# BluetoothAdapter4_0.net
KiCad netlist of a schematic drawn in Altium Designer
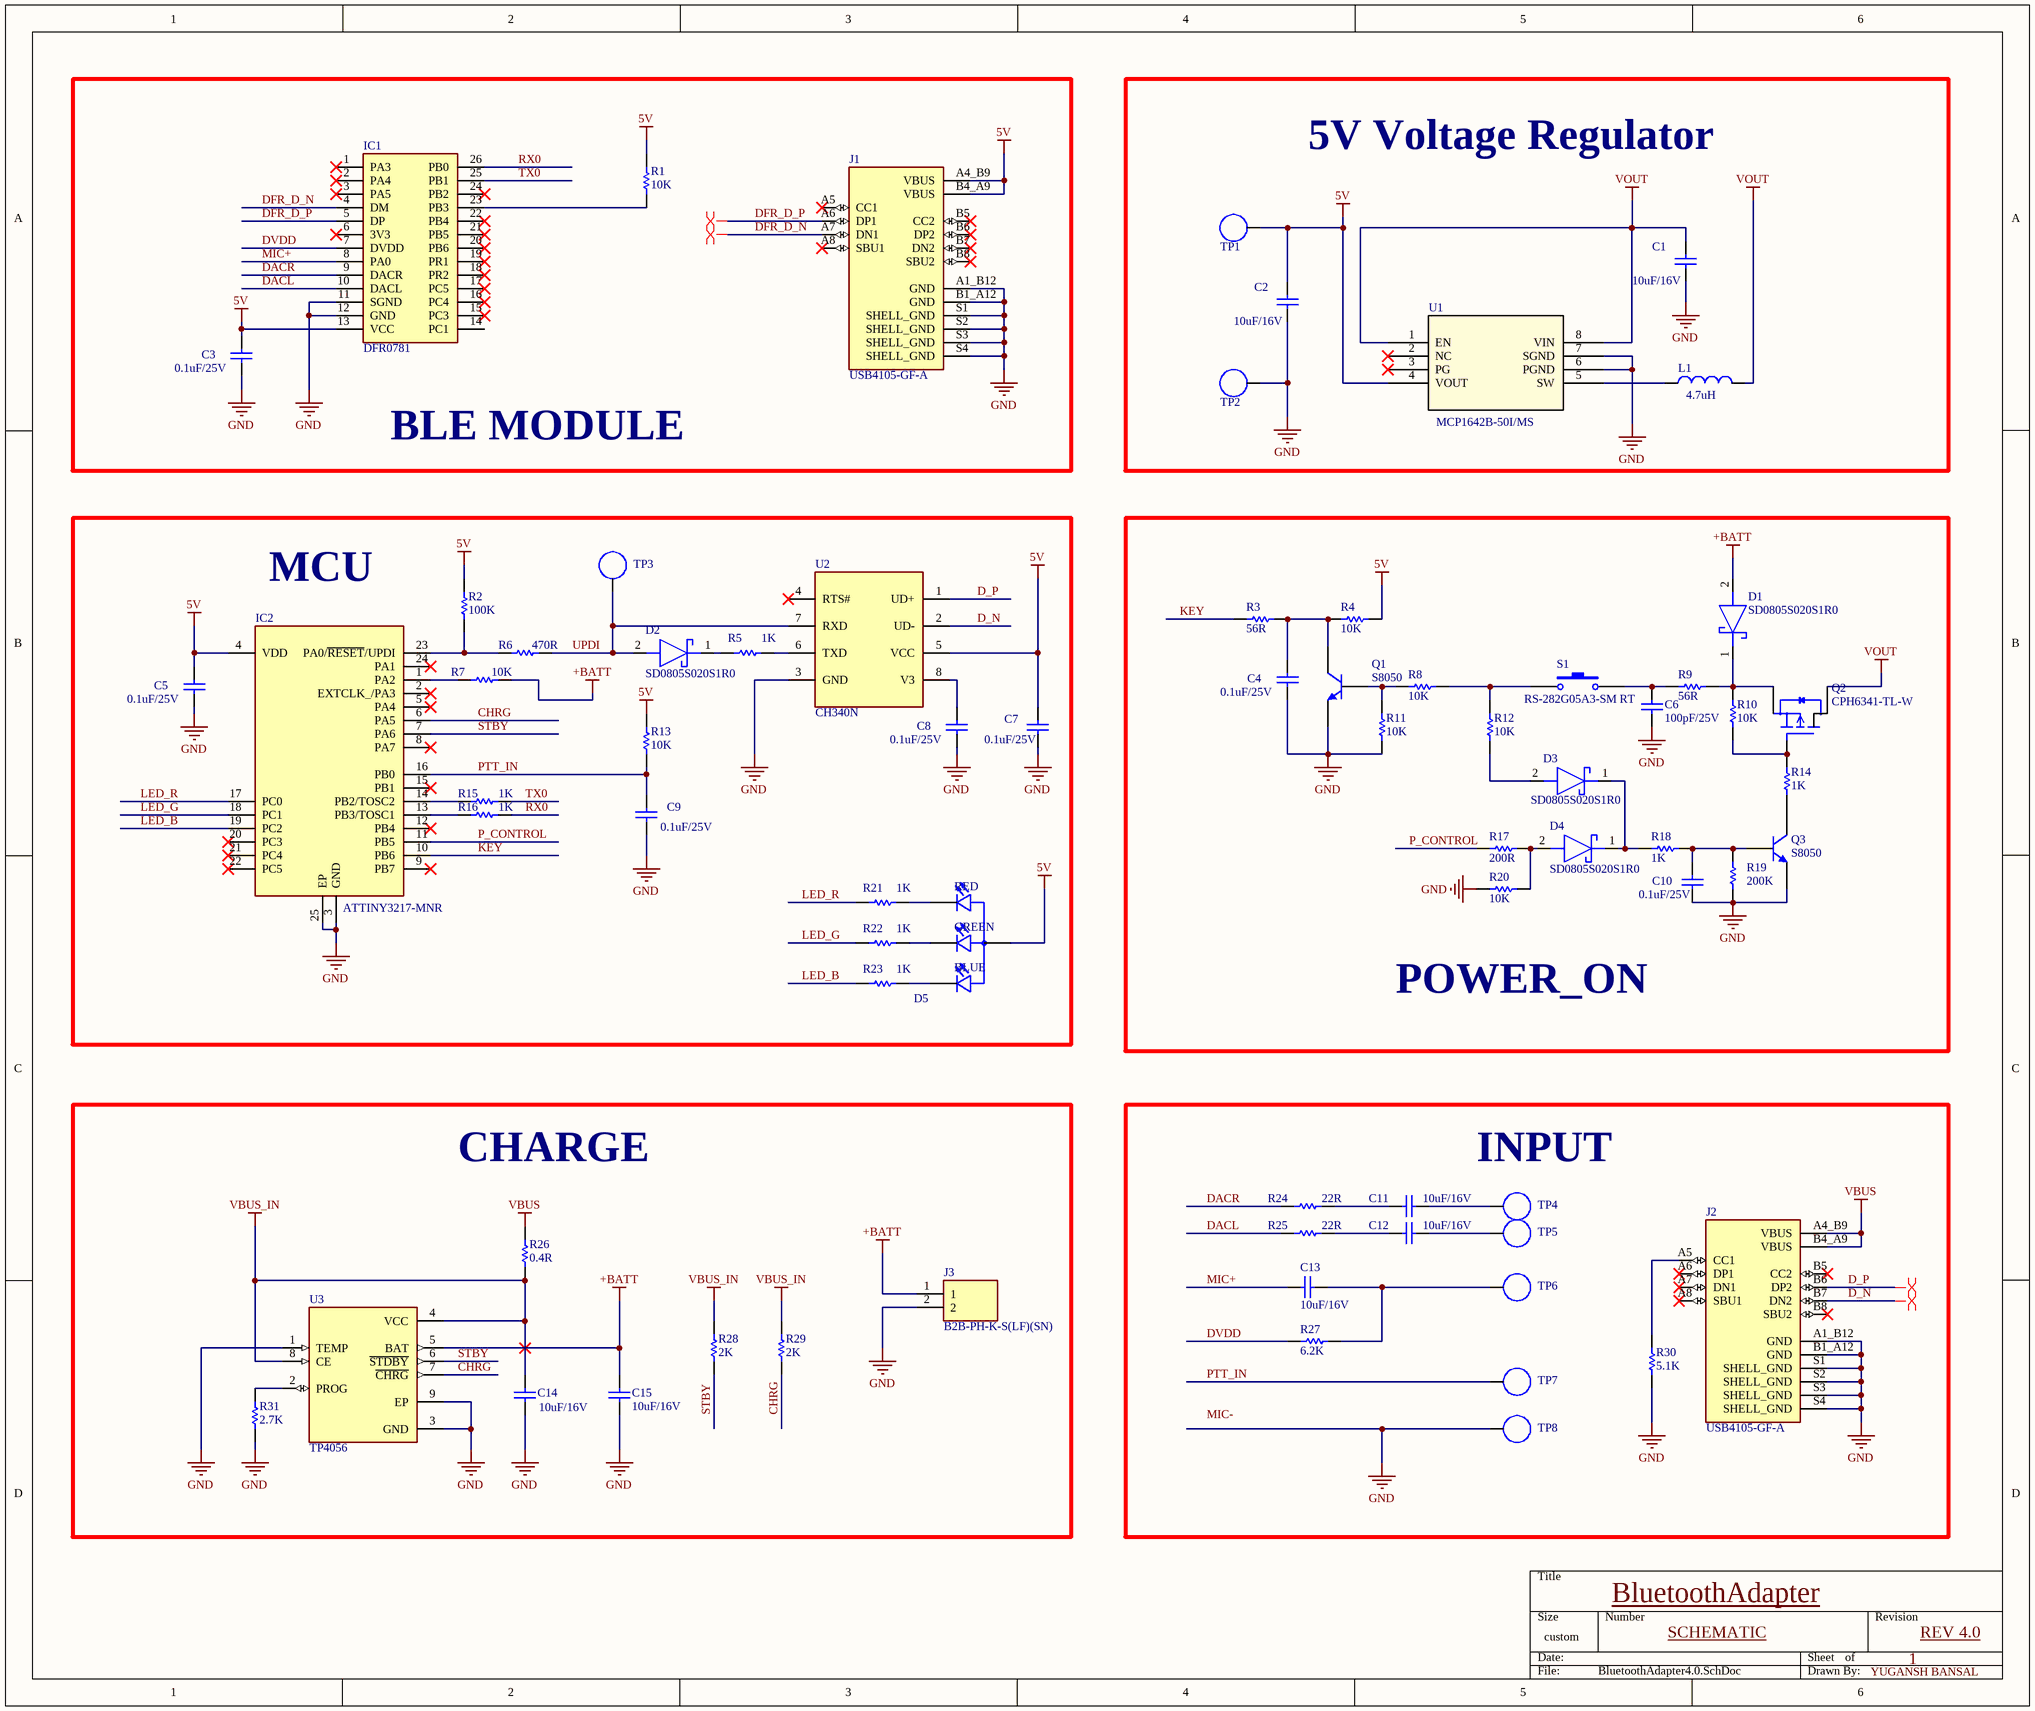
[diagram p0: BluetoothAdapter4.0.SchDoc]

(export (version "E")
  (design (tool "Eeschema 10.0.6"))
  (components
    (comp (ref "C1")
      (value "10uF/16V")
      (footprint "BluetoothAdapter:C0603S")
      (description "10 µF ±20% 16V Ceramic Capacitor X5R 0603 (1608 Metric)")
      (fields
        (field (name "MANUFACTURER") "Murata Electronics")
        (field (name "DIGI-KEY PART NUMBER") "490-10729-6-ND")
      )
      (libsource (lib "myLib") (part "Cap"))
    )
    (comp (ref "C2")
      (value "10uF/16V")
      (footprint "BluetoothAdapter:C0603S")
      (description "10 µF ±20% 16V Ceramic Capacitor X5R 0603 (1608 Metric)")
      (fields
        (field (name "MANUFACTURER") "Murata Electronics")
        (field (name "DIGI-KEY PART NUMBER") "490-10729-6-ND")
      )
      (libsource (lib "myLib") (part "Cap"))
    )
    (comp (ref "C3")
      (value "0.1uF/25V")
      (footprint "BluetoothAdapter:C0603S")
      (description "0.1 µF ±10% 25V Ceramic Capacitor X7R 0603 (1608 Metric)")
      (fields
        (field (name "MANUFACTURER") "KEMET")
        (field (name "DIGI-KEY PART NUMBER") "399-C0603C104K3RAC7867TR-ND")
      )
      (libsource (lib "myLib") (part "Cap"))
    )
    (comp (ref "C4")
      (value "0.1uF/25V")
      (footprint "BluetoothAdapter:C0603S")
      (description "0.1 µF ±10% 25V Ceramic Capacitor X7R 0603 (1608 Metric)")
      (fields
        (field (name "MANUFACTURER") "KEMET")
        (field (name "DIGI-KEY PART NUMBER") "399-C0603C104K3RAC7867TR-ND")
      )
      (libsource (lib "myLib") (part "Cap"))
    )
    (comp (ref "C5")
      (value "0.1uF/25V")
      (footprint "BluetoothAdapter:C0603S")
      (description "0.1 µF ±10% 25V Ceramic Capacitor X7R 0603 (1608 Metric)")
      (fields
        (field (name "MANUFACTURER") "KEMET")
        (field (name "DIGI-KEY PART NUMBER") "399-C0603C104K3RAC7867TR-ND")
      )
      (libsource (lib "myLib") (part "Cap"))
    )
    (comp (ref "C6")
      (value "100pF/25V")
      (footprint "BluetoothAdapter:C0603S")
      (description "0.1 µF ±10% 25V Ceramic Capacitor X7R 0603 (1608 Metric)")
      (fields
        (field (name "MANUFACTURER") "KEMET")
        (field (name "DIGI-KEY PART NUMBER") "399-C0603C101K3RACAUTODKR-ND")
      )
      (libsource (lib "myLib") (part "Cap"))
    )
    (comp (ref "C7")
      (value "0.1uF/25V")
      (footprint "BluetoothAdapter:C0603S")
      (description "0.1 µF ±10% 25V Ceramic Capacitor X7R 0603 (1608 Metric)")
      (fields
        (field (name "MANUFACTURER") "KEMET")
        (field (name "DIGI-KEY PART NUMBER") "399-C0603C104K3RAC7867TR-ND")
      )
      (libsource (lib "myLib") (part "Cap"))
    )
    (comp (ref "C8")
      (value "0.1uF/25V")
      (footprint "BluetoothAdapter:C0603S")
      (description "0.1 µF ±10% 25V Ceramic Capacitor X7R 0603 (1608 Metric)")
      (fields
        (field (name "MANUFACTURER") "KEMET")
        (field (name "DIGI-KEY PART NUMBER") "399-C0603C104K3RAC7867TR-ND")
      )
      (libsource (lib "myLib") (part "Cap"))
    )
    (comp (ref "C9")
      (value "0.1uF/25V")
      (footprint "BluetoothAdapter:C0603S")
      (description "0.1 µF ±10% 25V Ceramic Capacitor X7R 0603 (1608 Metric)")
      (fields
        (field (name "MANUFACTURER") "KEMET")
        (field (name "DIGI-KEY PART NUMBER") "399-C0603C104K3RAC7867TR-ND")
      )
      (libsource (lib "myLib") (part "Cap"))
    )
    (comp (ref "C10")
      (value "0.1uF/25V")
      (footprint "BluetoothAdapter:C0603S")
      (description "0.1 µF ±10% 25V Ceramic Capacitor X7R 0603 (1608 Metric)")
      (fields
        (field (name "MANUFACTURER") "KEMET")
        (field (name "DIGI-KEY PART NUMBER") "399-C0603C104K3RAC7867TR-ND")
      )
      (libsource (lib "myLib") (part "Cap"))
    )
    (comp (ref "C11")
      (value "10uF/16V")
      (footprint "BluetoothAdapter:C0603S")
      (description "10 µF ±20% 16V Ceramic Capacitor X5R 0603 (1608 Metric)")
      (fields
        (field (name "MANUFACTURER") "Murata Electronics")
        (field (name "DIGI-KEY PART NUMBER") "490-10729-6-ND")
      )
      (libsource (lib "myLib") (part "Cap"))
    )
    (comp (ref "C12")
      (value "10uF/16V")
      (footprint "BluetoothAdapter:C0603S")
      (description "10 µF ±20% 16V Ceramic Capacitor X5R 0603 (1608 Metric)")
      (fields
        (field (name "MANUFACTURER") "Murata Electronics")
        (field (name "DIGI-KEY PART NUMBER") "490-10729-6-ND")
      )
      (libsource (lib "myLib") (part "Cap"))
    )
    (comp (ref "C13")
      (value "10uF/16V")
      (footprint "BluetoothAdapter:C0603S")
      (description "10 µF ±20% 16V Ceramic Capacitor X5R 0603 (1608 Metric)")
      (fields
        (field (name "MANUFACTURER") "Murata Electronics")
        (field (name "DIGI-KEY PART NUMBER") "490-10729-6-ND")
      )
      (libsource (lib "myLib") (part "Cap"))
    )
    (comp (ref "C14")
      (value "10uF/16V")
      (footprint "BluetoothAdapter:C0603S")
      (description "10 µF ±20% 16V Ceramic Capacitor X5R 0603 (1608 Metric)")
      (fields
        (field (name "MANUFACTURER") "Murata Electronics")
        (field (name "DIGI-KEY PART NUMBER") "490-10729-6-ND")
      )
      (libsource (lib "myLib") (part "Cap"))
    )
    (comp (ref "C15")
      (value "10uF/16V")
      (footprint "BluetoothAdapter:C0603S")
      (description "10 µF ±20% 16V Ceramic Capacitor X5R 0603 (1608 Metric)")
      (fields
        (field (name "MANUFACTURER") "Murata Electronics")
        (field (name "DIGI-KEY PART NUMBER") "490-10729-6-ND")
      )
      (libsource (lib "myLib") (part "Cap"))
    )
    (comp (ref "D1")
      (value "SD0805S020S1R0")
      (footprint "BluetoothAdapter:DIOM1613X100N")
      (description "Diode 20 V 1A Surface Mount 0805 (2012 Metric)")
      (fields (field (name "MANUFACTURER") "AVX") (field (name "DIGI-KEY PART NUMBER") "581-SD0805S020S1R0"))
      (libsource (lib "*") (part "SD0805S020S1R0"))
    )
    (comp (ref "D2")
      (value "SD0805S020S1R0")
      (footprint "BluetoothAdapter:DIOM1613X100N")
      (description "Diode 20 V 1A Surface Mount 0805 (2012 Metric)")
      (fields (field (name "MANUFACTURER") "AVX") (field (name "DIGI-KEY PART NUMBER") "581-SD0805S020S1R0"))
      (libsource (lib "*") (part "SD0805S020S1R0"))
    )
    (comp (ref "D3")
      (value "SD0805S020S1R0")
      (footprint "BluetoothAdapter:DIOM1613X100N")
      (description "Diode 20 V 1A Surface Mount 0805 (2012 Metric)")
      (fields (field (name "MANUFACTURER") "AVX") (field (name "DIGI-KEY PART NUMBER") "581-SD0805S020S1R0"))
      (libsource (lib "*") (part "SD0805S020S1R0"))
    )
    (comp (ref "D4")
      (value "SD0805S020S1R0")
      (footprint "BluetoothAdapter:DIOM1613X100N")
      (description "Diode 20 V 1A Surface Mount 0805 (2012 Metric)")
      (fields (field (name "MANUFACTURER") "AVX") (field (name "DIGI-KEY PART NUMBER") "581-SD0805S020S1R0"))
      (libsource (lib "*") (part "SD0805S020S1R0"))
    )
    (comp (ref "D5")
      (value "LED RGB MIXED WHITE ( 1.6(L)X1.6")
      (footprint "BluetoothAdapter:LED_B38G3RGB-10D0003H2U1930")
      (description "Red, Green, Blue (RGB) LED Indication - Discrete 2V Red, 3V Green, 3V Blue 0606 (1616 Metric)")
      (fields
        (field (name "MANUFACTURER") "Harvatek Corporation")
        (field (name "DIGI-KEY PART NUMBER") "3147-B38G3RGB-10D0003H2U1930DKR-ND")
      )
      (libsource (lib "BluetoothAdapter") (part "B38G3RGB-10D0003H2U1930"))
    )
    (comp (ref "IC1")
      (value "DFR0781")
      (footprint "BluetoothAdapter:DFR0781")
      (description "Bluetooth Bluetooth v5.0 Transceiver Module Antenna Not Included Surface Mount")
      (fields (field (name "MANUFACTURER") "DFRobot") (field (name "DIGI-KEY PART NUMBER") "1738-DFR0781-ND"))
      (libsource (lib "BluetoothAdapter") (part "DFR0781"))
    )
    (comp (ref "IC2")
      (value "ATTINY3217-MNR")
      (footprint "BluetoothAdapter:QFN50P400X400X90-25N-D")
      (fields
        (field (name "MANUFACTURER") "Microchip")
        (field (name "DIGI-KEY PART NUMBER") "ATTINY3217-MNRDKR-ND")
        (field (name "Comment") "IC MCU 8BIT 32KB FLASH 24VQFN")
      )
      (libsource (lib "BluetoothAdapter") (part "ATTINY3217-MNR"))
    )
    (comp (ref "J1")
      (value "USB4105-GF-A")
      (footprint "BluetoothAdapter:GCT_USB4105-GF-A")
      (fields
        (field (name "MANUFACTURER") "GCT")
        (field (name "DIGI-KEY PART NUMBER") "2073-USB4105-GF-ADKR-ND")
        (field (name "Comment") "CONN RCP USB2.0 TYP C 24P SMD RA")
      )
      (libsource (lib "BluetoothAdapter") (part "USB4105-GF-A"))
    )
    (comp (ref "J2")
      (value "USB4105-GF-A")
      (footprint "BluetoothAdapter:GCT_USB4105-GF-A")
      (fields
        (field (name "MANUFACTURER") "GCT")
        (field (name "DIGI-KEY PART NUMBER") "2073-USB4105-GF-ADKR-ND")
        (field (name "Comment") "CONN RCP USB2.0 TYP C 24P SMD RA")
      )
      (libsource (lib "BluetoothAdapter") (part "USB4105-GF-A"))
    )
    (comp (ref "J3")
      (value "B2B-PH-K-S(LF)(SN)")
      (footprint "BluetoothAdapter:SHDR2W50P0X200_1X2_590X450X600P")
      (description "Connector Header Through Hole 2 position 0.079\" (2.00mm)")
      (fields
        (field (name "MANUFACTURER") "JST Sales America Inc.")
        (field (name "DIGI-KEY PART NUMBER") "455-1704-ND")
      )
      (libsource (lib "BluetoothAdapter") (part "B2B-PH-K-S(LF)(SN)"))
    )
    (comp (ref "L1")
      (value "4.7uH")
      (footprint "BluetoothAdapter:INDC2520X100N")
      (description "4.7 µH Shielded Multilayer Inductor 1.3 A 120mOhm 1008 (2520 Metric)")
      (fields
        (field (name "MANUFACTURER") "Abracon LLC")
        (field (name "DIGI-KEY PART NUMBER") "535-12797-6-ND")
      )
      (libsource (lib "Blueguard") (part "AIML-1008HC-4R7M-T"))
    )
    (comp (ref "Q1")
      (value "S8050")
      (footprint "BluetoothAdapter:SOT23-3D")
      (description "Bipolar (BJT) Transistor NPN 25 V 500 mA 150MHz 300 mW Surface Mount SOT-23")
      (fields (field (name "MANUFACTURER") "MDD") (field (name "DIGI-KEY PART NUMBER") "3372-S8050TR-ND"))
      (libsource (lib "BluetoothAdapter") (part "S8050"))
    )
    (comp (ref "Q2")
      (value "CPH6341-TL-W")
      (footprint "BluetoothAdapter:SOT95P285X140-6N")
      (description "P-Channel 30 V 5A (Ta) 1.6W (Ta) Surface Mount 6-CPH")
      (fields
        (field (name "MANUFACTURER") "onsemi")
        (field (name "DIGI-KEY PART NUMBER") "CPH6341-TL-WOSDKR-ND")
      )
      (libsource (lib "BluetoothAdapter") (part "CPH6341-TL-W"))
    )
    (comp (ref "Q3")
      (value "S8050")
      (footprint "BluetoothAdapter:SOT23-3D")
      (description "Bipolar (BJT) Transistor NPN 25 V 500 mA 150MHz 300 mW Surface Mount SOT-23")
      (fields (field (name "MANUFACTURER") "MDD") (field (name "DIGI-KEY PART NUMBER") "3372-S8050TR-ND"))
      (libsource (lib "BluetoothAdapter") (part "S8050"))
    )
    (comp (ref "R1")
      (value "10K")
      (footprint "BluetoothAdapter:R0603S")
      (description "10 kOhms ±1% 0.1W, 1/10W Chip Resistor 0603 (1608 Metric) Moisture Resistant Thick Film")
      (fields (field (name "MANUFACTURER") "YAGEO") (field (name "DIGI-KEY PART NUMBER") "311-10.0KHRCT-ND"))
      (libsource (lib "dif") (part "R0603"))
    )
    (comp (ref "R2")
      (value "100K")
      (footprint "BluetoothAdapter:R0603S")
      (description "100 kOhms ±1% 0.1W, 1/10W Chip Resistor 0603 (1608 Metric) Moisture Resistant Thick Film")
      (fields (field (name "MANUFACTURER") "YAGEO") (field (name "DIGI-KEY PART NUMBER") "311-100KHRDKR-ND"))
      (libsource (lib "dif") (part "R0603"))
    )
    (comp (ref "R3")
      (value "56R")
      (footprint "BluetoothAdapter:R0603S")
      (description "1 kOhms ±1% 0.1W, 1/10W Chip Resistor 0603 (1608 Metric) Moisture Resistant Thick Film")
      (fields (field (name "MANUFACTURER") "YAGEO") (field (name "DIGI-KEY PART NUMBER") "311-56.0HRDKR-ND"))
      (libsource (lib "dif") (part "R0603"))
    )
    (comp (ref "R4")
      (value "10K")
      (footprint "BluetoothAdapter:R0603S")
      (description "10 kOhms ±1% 0.1W, 1/10W Chip Resistor 0603 (1608 Metric) Moisture Resistant Thick Film")
      (fields (field (name "MANUFACTURER") "YAGEO") (field (name "DIGI-KEY PART NUMBER") "311-10.0KHRCT-ND"))
      (libsource (lib "dif") (part "R0603"))
    )
    (comp (ref "R5")
      (value "1K")
      (footprint "BluetoothAdapter:R0603S")
      (description "1 kOhms ±1% 0.1W, 1/10W Chip Resistor 0603 (1608 Metric) Moisture Resistant Thick Film")
      (fields (field (name "MANUFACTURER") "YAGEO") (field (name "DIGI-KEY PART NUMBER") "311-1.00KHRTR-ND"))
      (libsource (lib "dif") (part "R0603"))
    )
    (comp (ref "R6")
      (value "470R")
      (footprint "BluetoothAdapter:R0603S")
      (description "470 Ohms ±1% 0.1W, 1/10W Chip Resistor 0603 (1608 Metric) Moisture Resistant Thick Film")
      (fields (field (name "MANUFACTURER") "YAGEO") (field (name "DIGI-KEY PART NUMBER") "311-470HRDKR-ND"))
      (libsource (lib "dif") (part "R0603"))
    )
    (comp (ref "R7")
      (value "10K")
      (footprint "BluetoothAdapter:R0603S")
      (description "10 kOhms ±1% 0.1W, 1/10W Chip Resistor 0603 (1608 Metric) Moisture Resistant Thick Film")
      (fields (field (name "MANUFACTURER") "YAGEO") (field (name "DIGI-KEY PART NUMBER") "311-10.0KHRCT-ND"))
      (libsource (lib "dif") (part "R0603"))
    )
    (comp (ref "R8")
      (value "10K")
      (footprint "BluetoothAdapter:R0603S")
      (description "10 kOhms ±1% 0.1W, 1/10W Chip Resistor 0603 (1608 Metric) Moisture Resistant Thick Film")
      (fields (field (name "MANUFACTURER") "YAGEO") (field (name "DIGI-KEY PART NUMBER") "311-10.0KHRCT-ND"))
      (libsource (lib "dif") (part "R0603"))
    )
    (comp (ref "R9")
      (value "56R")
      (footprint "BluetoothAdapter:R0603S")
      (description "1 kOhms ±1% 0.1W, 1/10W Chip Resistor 0603 (1608 Metric) Moisture Resistant Thick Film")
      (fields (field (name "MANUFACTURER") "YAGEO") (field (name "DIGI-KEY PART NUMBER") "311-56.0HRDKR-ND"))
      (libsource (lib "dif") (part "R0603"))
    )
    (comp (ref "R10")
      (value "10K")
      (footprint "BluetoothAdapter:R0603S")
      (description "10 kOhms ±1% 0.1W, 1/10W Chip Resistor 0603 (1608 Metric) Moisture Resistant Thick Film")
      (fields (field (name "MANUFACTURER") "YAGEO") (field (name "DIGI-KEY PART NUMBER") "311-10.0KHRCT-ND"))
      (libsource (lib "dif") (part "R0603"))
    )
    (comp (ref "R11")
      (value "10K")
      (footprint "BluetoothAdapter:R0603S")
      (description "10 kOhms ±1% 0.1W, 1/10W Chip Resistor 0603 (1608 Metric) Moisture Resistant Thick Film")
      (fields (field (name "MANUFACTURER") "YAGEO") (field (name "DIGI-KEY PART NUMBER") "311-10.0KHRCT-ND"))
      (libsource (lib "dif") (part "R0603"))
    )
    (comp (ref "R12")
      (value "10K")
      (footprint "BluetoothAdapter:R0603S")
      (description "10 kOhms ±1% 0.1W, 1/10W Chip Resistor 0603 (1608 Metric) Moisture Resistant Thick Film")
      (fields (field (name "MANUFACTURER") "YAGEO") (field (name "DIGI-KEY PART NUMBER") "311-10.0KHRCT-ND"))
      (libsource (lib "dif") (part "R0603"))
    )
    (comp (ref "R13")
      (value "10K")
      (footprint "BluetoothAdapter:R0603S")
      (description "10 kOhms ±1% 0.1W, 1/10W Chip Resistor 0603 (1608 Metric) Moisture Resistant Thick Film")
      (fields (field (name "MANUFACTURER") "YAGEO") (field (name "DIGI-KEY PART NUMBER") "311-10.0KHRCT-ND"))
      (libsource (lib "dif") (part "R0603"))
    )
    (comp (ref "R14")
      (value "1K")
      (footprint "BluetoothAdapter:R0603S")
      (description "1 kOhms ±1% 0.1W, 1/10W Chip Resistor 0603 (1608 Metric) Moisture Resistant Thick Film")
      (fields (field (name "MANUFACTURER") "YAGEO") (field (name "DIGI-KEY PART NUMBER") "311-1.00KHRTR-ND"))
      (libsource (lib "dif") (part "R0603"))
    )
    (comp (ref "R15")
      (value "1K")
      (footprint "BluetoothAdapter:R0603S")
      (description "1 kOhms ±1% 0.1W, 1/10W Chip Resistor 0603 (1608 Metric) Moisture Resistant Thick Film")
      (fields (field (name "MANUFACTURER") "YAGEO") (field (name "DIGI-KEY PART NUMBER") "311-1.00KHRTR-ND"))
      (libsource (lib "dif") (part "R0603"))
    )
    (comp (ref "R16")
      (value "1K")
      (footprint "BluetoothAdapter:R0603S")
      (description "1 kOhms ±1% 0.1W, 1/10W Chip Resistor 0603 (1608 Metric) Moisture Resistant Thick Film")
      (fields (field (name "MANUFACTURER") "YAGEO") (field (name "DIGI-KEY PART NUMBER") "311-1.00KHRTR-ND"))
      (libsource (lib "dif") (part "R0603"))
    )
    (comp (ref "R17")
      (value "200R")
      (footprint "BluetoothAdapter:R0603S")
      (description "10 kOhms ±1% 0.1W, 1/10W Chip Resistor 0603 (1608 Metric) Moisture Resistant Thick Film")
      (fields (field (name "MANUFACTURER") "YAGEO") (field (name "DIGI-KEY PART NUMBER") "311-200HRDKR-ND"))
      (libsource (lib "dif") (part "R0603"))
    )
    (comp (ref "R18")
      (value "1K")
      (footprint "BluetoothAdapter:R0603S")
      (description "1 kOhms ±1% 0.1W, 1/10W Chip Resistor 0603 (1608 Metric) Moisture Resistant Thick Film")
      (fields (field (name "MANUFACTURER") "YAGEO") (field (name "DIGI-KEY PART NUMBER") "311-1.00KHRTR-ND"))
      (libsource (lib "dif") (part "R0603"))
    )
    (comp (ref "R19")
      (value "200K")
      (footprint "BluetoothAdapter:R0603S")
      (description "200 kOhms ±1% 0.1W, 1/10W Chip Resistor 0603 (1608 Metric) Moisture Resistant Thick Film")
      (fields
        (field (name "MANUFACTURER") "YAGEO")
        (field (name "DIGI-KEY PART NUMBER") "13-RC0603FR-10200KLDKR-ND")
      )
      (libsource (lib "dif") (part "R0603"))
    )
    (comp (ref "R20")
      (value "10K")
      (footprint "BluetoothAdapter:R0603S")
      (description "10 kOhms ±1% 0.1W, 1/10W Chip Resistor 0603 (1608 Metric) Moisture Resistant Thick Film")
      (fields (field (name "MANUFACTURER") "YAGEO") (field (name "DIGI-KEY PART NUMBER") "311-10.0KHRCT-ND"))
      (libsource (lib "dif") (part "R0603"))
    )
    (comp (ref "R21")
      (value "1K")
      (footprint "BluetoothAdapter:R0603S")
      (description "1 kOhms ±1% 0.1W, 1/10W Chip Resistor 0603 (1608 Metric) Moisture Resistant Thick Film")
      (fields (field (name "MANUFACTURER") "YAGEO") (field (name "DIGI-KEY PART NUMBER") "311-1.00KHRTR-ND"))
      (libsource (lib "dif") (part "R0603"))
    )
    (comp (ref "R22")
      (value "1K")
      (footprint "BluetoothAdapter:R0603S")
      (description "1 kOhms ±1% 0.1W, 1/10W Chip Resistor 0603 (1608 Metric) Moisture Resistant Thick Film")
      (fields (field (name "MANUFACTURER") "YAGEO") (field (name "DIGI-KEY PART NUMBER") "311-1.00KHRTR-ND"))
      (libsource (lib "dif") (part "R0603"))
    )
    (comp (ref "R23")
      (value "1K")
      (footprint "BluetoothAdapter:R0603S")
      (description "1 kOhms ±1% 0.1W, 1/10W Chip Resistor 0603 (1608 Metric) Moisture Resistant Thick Film")
      (fields (field (name "MANUFACTURER") "YAGEO") (field (name "DIGI-KEY PART NUMBER") "311-1.00KHRTR-ND"))
      (libsource (lib "dif") (part "R0603"))
    )
    (comp (ref "R24")
      (value "22R")
      (footprint "BluetoothAdapter:R0603S")
      (description "22 Ohms ±5% 0.1W, 1/10W Chip Resistor 0603 (1608 Metric) Moisture Resistant Thick Film")
      (fields (field (name "MANUFACTURER") "YAGEO") (field (name "DIGI-KEY PART NUMBER") "311-22GRDKR-ND"))
      (libsource (lib "dif") (part "R0603"))
    )
    (comp (ref "R25")
      (value "22R")
      (footprint "BluetoothAdapter:R0603S")
      (description "22 Ohms ±5% 0.1W, 1/10W Chip Resistor 0603 (1608 Metric) Moisture Resistant Thick Film")
      (fields (field (name "MANUFACTURER") "YAGEO") (field (name "DIGI-KEY PART NUMBER") "311-22GRDKR-ND"))
      (libsource (lib "dif") (part "R0603"))
    )
    (comp (ref "R26")
      (value "0.4R")
      (footprint "BluetoothAdapter:R1206S")
      (fields
        (field (name "MANUFACTURER") "YAGEO")
        (field (name "DIGI-KEY PART NUMBER") "311-.4LWDKR-ND")
        (field (name "Comment") "RES 0.4 OHM 1% 1/4W 1206")
      )
      (libsource (lib "dif") (part "R0603"))
    )
    (comp (ref "R27")
      (value "6.2K")
      (footprint "BluetoothAdapter:R0603S")
      (description "6.2 kOhms ±1% 0.1W, 1/10W Chip Resistor 0603 (1608 Metric) Moisture Resistant Thick Film")
      (fields (field (name "MANUFACTURER") "YAGEO") (field (name "DIGI-KEY PART NUMBER") "311-6.20KHRDKR-ND"))
      (libsource (lib "dif") (part "R0603"))
    )
    (comp (ref "R28")
      (value "2K")
      (footprint "BluetoothAdapter:R0603S")
      (description "2 kOhms ±1% 0.1W, 1/10W Chip Resistor 0603 (1608 Metric) Moisture Resistant Thick Film")
      (fields (field (name "MANUFACTURER") "YAGEO") (field (name "DIGI-KEY PART NUMBER") "311-2.00KHRDKR-ND"))
      (libsource (lib "dif") (part "R0603"))
    )
    (comp (ref "R29")
      (value "2K")
      (footprint "BluetoothAdapter:R0603S")
      (description "2 kOhms ±1% 0.1W, 1/10W Chip Resistor 0603 (1608 Metric) Moisture Resistant Thick Film")
      (fields (field (name "MANUFACTURER") "YAGEO") (field (name "DIGI-KEY PART NUMBER") "311-2.00KHRDKR-ND"))
      (libsource (lib "dif") (part "R0603"))
    )
    (comp (ref "R30")
      (value "5.1K")
      (footprint "BluetoothAdapter:R0603S")
      (description "5.1kOhms ±1% 0.1W, 1/10W Chip Resistor 0603 (1608 Metric) Moisture Resistant Thick Film")
      (fields (field (name "MANUFACTURER") "YAGEO") (field (name "DIGI-KEY PART NUMBER") "311-5.10KHRDKR-ND"))
      (libsource (lib "dif") (part "R0603"))
    )
    (comp (ref "R31")
      (value "2.7K")
      (footprint "BluetoothAdapter:R0603S")
      (description "2.7 kOhms ±1% 0.1W, 1/10W Chip Resistor 0603 (1608 Metric) Moisture Resistant Thick Film")
      (fields (field (name "MANUFACTURER") "YAGEO") (field (name "DIGI-KEY PART NUMBER") "311-2.70KHRDKR-ND"))
      (libsource (lib "dif") (part "R0603"))
    )
    (comp (ref "S1")
      (value "RS-282G05A3-SM RT")
      (footprint "BluetoothAdapter:RS282G05A3SMRT")
      (description "Tactile Switch SPST-NO Top Actuated Surface Mount")
      (fields
        (field (name "MANUFACTURER") "C & K COMPONENTS")
        (field (name "DIGI-KEY PART NUMBER") "CKN10384DKR-ND")
      )
      (libsource (lib "BluetoothAdapter") (part "RS282G05A3SMRT"))
    )
    (comp (ref "TP1")
      (value "TP")
      (footprint "BluetoothAdapter:TP")
      (libsource (lib "BluetoothAdapter") (part "TP"))
    )
    (comp (ref "TP2")
      (value "TP")
      (footprint "BluetoothAdapter:TP")
      (libsource (lib "BluetoothAdapter") (part "TP"))
    )
    (comp (ref "TP3")
      (value "TP")
      (footprint "BluetoothAdapter:TP")
      (libsource (lib "BluetoothAdapter") (part "TP"))
    )
    (comp (ref "TP4")
      (value "TP")
      (footprint "BluetoothAdapter:TP")
      (libsource (lib "BluetoothAdapter") (part "TP"))
    )
    (comp (ref "TP5")
      (value "TP")
      (footprint "BluetoothAdapter:TP")
      (libsource (lib "BluetoothAdapter") (part "TP"))
    )
    (comp (ref "TP6")
      (value "TP")
      (footprint "BluetoothAdapter:TP")
      (libsource (lib "BluetoothAdapter") (part "TP"))
    )
    (comp (ref "TP7")
      (value "TP")
      (footprint "BluetoothAdapter:TP")
      (libsource (lib "BluetoothAdapter") (part "TP"))
    )
    (comp (ref "TP8")
      (value "TP")
      (footprint "BluetoothAdapter:TP")
      (libsource (lib "BluetoothAdapter") (part "TP"))
    )
    (comp (ref "U1")
      (value "MCP1642B-50I/MS")
      (footprint "BluetoothAdapter:MCP1642B-50I/MS")
      (fields
        (field (name "MANUFACTURER") "Microchip Technology")
        (field (name "DIGI-KEY PART NUMBER") "MCP1642B-50I/MS-ND")
        (field (name "Comment") "IC REG BOOST 5V 800MA 8MSOP")
      )
      (libsource (lib "Blueguard") (part "MCP1642B-50I/MS"))
    )
    (comp (ref "U2")
      (value "CH340N")
      (footprint "BluetoothAdapter:SOIC127P602X173-8N")
      (description "IC USB TO UART BRIDGE SOP-8")
      (fields
        (field (name "MANUFACTURER") "WCH(Jiangsu Qin Heng)")
        (field (name "DIGI-KEY PART NUMBER") "C506813")
      )
      (libsource (lib "BluetoothAdapter") (part "CH340N"))
    )
    (comp (ref "U3")
      (value "TP4056")
      (footprint "BluetoothAdapter:SOP127P600X175-9N")
      (description "Complete single cell Li-Ion battery with a constant current / constant voltage linear charger")
      (fields
        (field (name "MANUFACTURER") "TPOWER semiconductor Co.,LTD.")
        (field (name "DIGI-KEY PART NUMBER") "C382139")
      )
      (libsource (lib "BluetoothAdapter") (part "TP4056"))
    )
  )
  (nets
    (net (code "1") (name "+BATT") (class "Default")
      (node (ref "C15") (pin "2") (pinfunction "2_2") (pintype "passive"))
      (node (ref "D1") (pin "2") (pinfunction "A_2") (pintype "passive"))
      (node (ref "J3") (pin "1") (pinfunction "1_1") (pintype "passive"))
      (node (ref "R7") (pin "2") (pinfunction "2_2") (pintype "passive"))
      (node (ref "U3") (pin "5") (pinfunction "BAT_5") (pintype "output"))
    )
    (net (code "2") (name "/CHRG") (class "Default")
      (node (ref "IC2") (pin "6") (pinfunction "PA5_6") (pintype "passive"))
      (node (ref "R29") (pin "2") (pinfunction "2_2") (pintype "passive"))
      (node (ref "U3") (pin "7") (pinfunction "~{CHRG}_7") (pintype "output"))
    )
    (net (code "3") (name "/DACL") (class "Default")
      (node (ref "IC1") (pin "10") (pinfunction "DACL_10") (pintype "passive"))
      (node (ref "R25") (pin "1") (pinfunction "1_1") (pintype "passive"))
    )
    (net (code "4") (name "/DACR") (class "Default")
      (node (ref "IC1") (pin "9") (pinfunction "DACR_9") (pintype "passive"))
      (node (ref "R24") (pin "1") (pinfunction "1_1") (pintype "passive"))
    )
    (net (code "5") (name "/DFR_D_N") (class "Default")
      (node (ref "IC1") (pin "4") (pinfunction "DM_4") (pintype "passive"))
      (node (ref "J1") (pin "A7") (pinfunction "DN1_A7") (pintype "bidirectional"))
    )
    (net (code "6") (name "/DFR_D_P") (class "Default")
      (node (ref "IC1") (pin "5") (pinfunction "DP_5") (pintype "passive"))
      (node (ref "J1") (pin "A6") (pinfunction "DP1_A6") (pintype "bidirectional"))
    )
    (net (code "7") (name "/DVDD") (class "Default")
      (node (ref "IC1") (pin "7") (pinfunction "DVDD_7") (pintype "passive"))
      (node (ref "R27") (pin "1") (pinfunction "1_1") (pintype "passive"))
    )
    (net (code "8") (name "/D_N") (class "Default")
      (node (ref "J2") (pin "B7") (pinfunction "DN2_B7") (pintype "bidirectional"))
      (node (ref "U2") (pin "2") (pinfunction "UD-_2") (pintype "passive"))
    )
    (net (code "9") (name "/D_P") (class "Default")
      (node (ref "J2") (pin "B6") (pinfunction "DP2_B6") (pintype "bidirectional"))
      (node (ref "U2") (pin "1") (pinfunction "UD+_1") (pintype "passive"))
    )
    (net (code "10") (name "/KEY") (class "Default")
      (node (ref "IC2") (pin "10") (pinfunction "PB6_10") (pintype "passive"))
      (node (ref "R3") (pin "1") (pinfunction "1_1") (pintype "passive"))
    )
    (net (code "11") (name "/LED_B") (class "Default")
      (node (ref "IC2") (pin "19") (pinfunction "PC2_19") (pintype "passive"))
      (node (ref "R23") (pin "1") (pinfunction "1_1") (pintype "passive"))
    )
    (net (code "12") (name "/LED_G") (class "Default")
      (node (ref "IC2") (pin "18") (pinfunction "PC1_18") (pintype "passive"))
      (node (ref "R22") (pin "1") (pinfunction "1_1") (pintype "passive"))
    )
    (net (code "13") (name "/LED_R") (class "Default")
      (node (ref "IC2") (pin "17") (pinfunction "PC0_17") (pintype "passive"))
      (node (ref "R21") (pin "1") (pinfunction "1_1") (pintype "passive"))
    )
    (net (code "14") (name "/MIC+") (class "Default")
      (node (ref "C13") (pin "2") (pinfunction "2_2") (pintype "passive"))
      (node (ref "IC1") (pin "8") (pinfunction "PA0_8") (pintype "passive"))
    )
    (net (code "16") (name "/PTT_IN") (class "Default")
      (node (ref "C9") (pin "1") (pinfunction "1_1") (pintype "passive"))
      (node (ref "IC2") (pin "16") (pinfunction "PB0_16") (pintype "passive"))
      (node (ref "R13") (pin "2") (pinfunction "2_2") (pintype "passive"))
      (node (ref "TP7") (pin "1") (pinfunction "1_1") (pintype "passive"))
    )
    (net (code "17") (name "/P_CONTROL") (class "Default")
      (node (ref "IC2") (pin "11") (pinfunction "PB5_11") (pintype "passive"))
      (node (ref "R17") (pin "1") (pinfunction "1_1") (pintype "passive"))
    )
    (net (code "18") (name "/RX0") (class "Default")
      (node (ref "IC1") (pin "26") (pinfunction "PB0_26") (pintype "passive"))
      (node (ref "R16") (pin "2") (pinfunction "2_2") (pintype "passive"))
    )
    (net (code "19") (name "/STBY") (class "Default")
      (node (ref "IC2") (pin "7") (pinfunction "PA6_7") (pintype "passive"))
      (node (ref "R28") (pin "2") (pinfunction "2_2") (pintype "passive"))
      (node (ref "U3") (pin "6") (pinfunction "~{STDBY}_6") (pintype "output"))
    )
    (net (code "20") (name "/TX0") (class "Default")
      (node (ref "IC1") (pin "25") (pinfunction "PB1_25") (pintype "passive"))
      (node (ref "R15") (pin "2") (pinfunction "2_2") (pintype "passive"))
    )
    (net (code "21") (name "/UPDI") (class "Default")
      (node (ref "D2") (pin "2") (pinfunction "A_2") (pintype "passive"))
      (node (ref "R6") (pin "1") (pinfunction "1_1") (pintype "passive"))
      (node (ref "TP3") (pin "1") (pinfunction "1_1") (pintype "passive"))
      (node (ref "U2") (pin "7") (pinfunction "RXD_7") (pintype "power_in"))
    )
    (net (code "22") (name "5V") (class "Default")
      (node (ref "C2") (pin "2") (pinfunction "2_2") (pintype "passive"))
      (node (ref "C3") (pin "1") (pinfunction "1_1") (pintype "passive"))
      (node (ref "C5") (pin "1") (pinfunction "1_1") (pintype "passive"))
      (node (ref "C7") (pin "1") (pinfunction "1_1") (pintype "passive"))
      (node (ref "D5") (pin "3") (pinfunction "A_3") (pintype "passive"))
      (node (ref "IC1") (pin "13") (pinfunction "VCC_13") (pintype "passive"))
      (node (ref "IC2") (pin "4") (pinfunction "VDD_4") (pintype "passive"))
      (node (ref "J1") (pin "A4_B9") (pinfunction "VBUS_A4_B9") (pintype "power_in"))
      (node (ref "J1") (pin "B4_A9") (pinfunction "VBUS_B4_A9") (pintype "power_in"))
      (node (ref "R1") (pin "2") (pinfunction "2_2") (pintype "passive"))
      (node (ref "R13") (pin "1") (pinfunction "1_1") (pintype "passive"))
      (node (ref "R2") (pin "1") (pinfunction "1_1") (pintype "passive"))
      (node (ref "R4") (pin "1") (pinfunction "1_1") (pintype "passive"))
      (node (ref "TP1") (pin "1") (pinfunction "1_1") (pintype "passive"))
      (node (ref "U1") (pin "4") (pinfunction "VOUT_4") (pintype "passive"))
      (node (ref "U2") (pin "5") (pinfunction "VCC_5") (pintype "passive"))
    )
    (net (code "23") (name "GND") (class "Default")
      (node (ref "C1") (pin "1") (pinfunction "1_1") (pintype "passive"))
      (node (ref "C10") (pin "2") (pinfunction "2_2") (pintype "passive"))
      (node (ref "C14") (pin "1") (pinfunction "1_1") (pintype "passive"))
      (node (ref "C15") (pin "1") (pinfunction "1_1") (pintype "passive"))
      (node (ref "C2") (pin "1") (pinfunction "1_1") (pintype "passive"))
      (node (ref "C3") (pin "2") (pinfunction "2_2") (pintype "passive"))
      (node (ref "C4") (pin "2") (pinfunction "2_2") (pintype "passive"))
      (node (ref "C5") (pin "2") (pinfunction "2_2") (pintype "passive"))
      (node (ref "C6") (pin "1") (pinfunction "1_1") (pintype "passive"))
      (node (ref "C7") (pin "2") (pinfunction "2_2") (pintype "passive"))
      (node (ref "C8") (pin "2") (pinfunction "2_2") (pintype "passive"))
      (node (ref "C9") (pin "2") (pinfunction "2_2") (pintype "passive"))
      (node (ref "IC1") (pin "11") (pinfunction "SGND_11") (pintype "passive"))
      (node (ref "IC1") (pin "12") (pinfunction "GND_12") (pintype "passive"))
      (node (ref "IC2") (pin "25") (pinfunction "EP_25") (pintype "passive"))
      (node (ref "IC2") (pin "3") (pinfunction "GND_3") (pintype "passive"))
      (node (ref "J1") (pin "A1_B12") (pinfunction "GND_A1_B12") (pintype "power_in"))
      (node (ref "J1") (pin "B1_A12") (pinfunction "GND_B1_A12") (pintype "power_in"))
      (node (ref "J1") (pin "S1") (pinfunction "SHELL_GND_S1") (pintype "power_in"))
      (node (ref "J1") (pin "S2") (pinfunction "SHELL_GND_S2") (pintype "power_in"))
      (node (ref "J1") (pin "S3") (pinfunction "SHELL_GND_S3") (pintype "power_in"))
      (node (ref "J1") (pin "S4") (pinfunction "SHELL_GND_S4") (pintype "power_in"))
      (node (ref "J2") (pin "A1_B12") (pinfunction "GND_A1_B12") (pintype "power_in"))
      (node (ref "J2") (pin "B1_A12") (pinfunction "GND_B1_A12") (pintype "power_in"))
      (node (ref "J2") (pin "S1") (pinfunction "SHELL_GND_S1") (pintype "power_in"))
      (node (ref "J2") (pin "S2") (pinfunction "SHELL_GND_S2") (pintype "power_in"))
      (node (ref "J2") (pin "S3") (pinfunction "SHELL_GND_S3") (pintype "power_in"))
      (node (ref "J2") (pin "S4") (pinfunction "SHELL_GND_S4") (pintype "power_in"))
      (node (ref "J3") (pin "2") (pinfunction "2_2") (pintype "passive"))
      (node (ref "Q1") (pin "3") (pinfunction "E_3") (pintype "passive"))
      (node (ref "Q3") (pin "3") (pinfunction "E_3") (pintype "passive"))
      (node (ref "R11") (pin "2") (pinfunction "2_2") (pintype "passive"))
      (node (ref "R19") (pin "1") (pinfunction "1_1") (pintype "passive"))
      (node (ref "R20") (pin "1") (pinfunction "1_1") (pintype "passive"))
      (node (ref "R30") (pin "2") (pinfunction "2_2") (pintype "passive"))
      (node (ref "R31") (pin "2") (pinfunction "2_2") (pintype "passive"))
      (node (ref "TP2") (pin "1") (pinfunction "1_1") (pintype "passive"))
      (node (ref "TP8") (pin "1") (pinfunction "1_1") (pintype "passive"))
      (node (ref "U1") (pin "6") (pinfunction "PGND_6") (pintype "passive"))
      (node (ref "U1") (pin "7") (pinfunction "SGND_7") (pintype "passive"))
      (node (ref "U2") (pin "3") (pinfunction "GND_3") (pintype "passive"))
      (node (ref "U3") (pin "1") (pinfunction "TEMP_1") (pintype "input"))
      (node (ref "U3") (pin "3") (pinfunction "GND_3") (pintype "power_in"))
      (node (ref "U3") (pin "9") (pinfunction "EP_9") (pintype "passive"))
    )
    (net (code "24") (name "Net-(C6-Pad2)") (class "Default")
      (node (ref "C6") (pin "2") (pinfunction "2_2") (pintype "passive"))
      (node (ref "R9") (pin "1") (pinfunction "1_1") (pintype "passive"))
      (node (ref "S1") (pin "2") (pinfunction "2_2") (pintype "passive"))
    )
    (net (code "25") (name "Net-(C11-Pad1)") (class "Default")
      (node (ref "C11") (pin "1") (pinfunction "1_1") (pintype "passive"))
      (node (ref "TP4") (pin "1") (pinfunction "1_1") (pintype "passive"))
    )
    (net (code "26") (name "Net-(C11-Pad2)") (class "Default")
      (node (ref "C11") (pin "2") (pinfunction "2_2") (pintype "passive"))
      (node (ref "R24") (pin "2") (pinfunction "2_2") (pintype "passive"))
    )
    (net (code "27") (name "Net-(C12-Pad1)") (class "Default")
      (node (ref "C12") (pin "1") (pinfunction "1_1") (pintype "passive"))
      (node (ref "TP5") (pin "1") (pinfunction "1_1") (pintype "passive"))
    )
    (net (code "28") (name "Net-(C12-Pad2)") (class "Default")
      (node (ref "C12") (pin "2") (pinfunction "2_2") (pintype "passive"))
      (node (ref "R25") (pin "2") (pinfunction "2_2") (pintype "passive"))
    )
    (net (code "29") (name "Net-(C13-Pad1)") (class "Default")
      (node (ref "C13") (pin "1") (pinfunction "1_1") (pintype "passive"))
      (node (ref "R27") (pin "2") (pinfunction "2_2") (pintype "passive"))
      (node (ref "TP6") (pin "1") (pinfunction "1_1") (pintype "passive"))
    )
    (net (code "30") (name "Net-(D1-K)") (class "Default")
      (node (ref "D1") (pin "1") (pinfunction "K_1") (pintype "passive"))
      (node (ref "Q2") (pin "4") (pinfunction "S_4") (pintype "passive"))
      (node (ref "R10") (pin "1") (pinfunction "1_1") (pintype "passive"))
      (node (ref "R9") (pin "2") (pinfunction "2_2") (pintype "passive"))
    )
    (net (code "31") (name "Net-(D2-K)") (class "Default")
      (node (ref "D2") (pin "1") (pinfunction "K_1") (pintype "passive"))
      (node (ref "R5") (pin "1") (pinfunction "1_1") (pintype "passive"))
    )
    (net (code "32") (name "Net-(D3-A)") (class "Default")
      (node (ref "D3") (pin "2") (pinfunction "A_2") (pintype "passive"))
      (node (ref "R12") (pin "2") (pinfunction "2_2") (pintype "passive"))
    )
    (net (code "33") (name "Net-(D3-K)") (class "Default")
      (node (ref "D3") (pin "1") (pinfunction "K_1") (pintype "passive"))
      (node (ref "D4") (pin "1") (pinfunction "K_1") (pintype "passive"))
      (node (ref "R18") (pin "2") (pinfunction "2_2") (pintype "passive"))
    )
    (net (code "34") (name "Net-(D4-A)") (class "Default")
      (node (ref "D4") (pin "2") (pinfunction "A_2") (pintype "passive"))
      (node (ref "R17") (pin "2") (pinfunction "2_2") (pintype "passive"))
      (node (ref "R20") (pin "2") (pinfunction "2_2") (pintype "passive"))
    )
    (net (code "35") (name "Net-(D5-B_C)") (class "Default")
      (node (ref "D5") (pin "2") (pinfunction "B_C_2") (pintype "passive"))
      (node (ref "R23") (pin "2") (pinfunction "2_2") (pintype "passive"))
    )
    (net (code "36") (name "Net-(D5-G_C)") (class "Default")
      (node (ref "D5") (pin "1") (pinfunction "G_C_1") (pintype "passive"))
      (node (ref "R22") (pin "2") (pinfunction "2_2") (pintype "passive"))
    )
    (net (code "37") (name "Net-(D5-R_C)") (class "Default")
      (node (ref "D5") (pin "4") (pinfunction "R_C_4") (pintype "passive"))
      (node (ref "R21") (pin "2") (pinfunction "2_2") (pintype "passive"))
    )
    (net (code "38") (name "Net-(IC1-PB3)") (class "Default")
      (node (ref "IC1") (pin "23") (pinfunction "PB3_23") (pintype "passive"))
      (node (ref "R1") (pin "1") (pinfunction "1_1") (pintype "passive"))
    )
    (net (code "39") (name "Net-(IC2-PA0{slash}~{RESET}{slash}UPDI)") (class "Default")
      (node (ref "IC2") (pin "23") (pinfunction "PA0/~{RESET}/UPDI_23") (pintype "passive"))
      (node (ref "R2") (pin "2") (pinfunction "2_2") (pintype "passive"))
      (node (ref "R6") (pin "2") (pinfunction "2_2") (pintype "passive"))
    )
    (net (code "40") (name "Net-(IC2-PA2)") (class "Default")
      (node (ref "IC2") (pin "1") (pinfunction "PA2_1") (pintype "passive"))
      (node (ref "R7") (pin "1") (pinfunction "1_1") (pintype "passive"))
    )
    (net (code "41") (name "Net-(IC2-PB2{slash}TOSC2)") (class "Default")
      (node (ref "IC2") (pin "14") (pinfunction "PB2/TOSC2_14") (pintype "passive"))
      (node (ref "R15") (pin "1") (pinfunction "1_1") (pintype "passive"))
    )
    (net (code "42") (name "Net-(IC2-PB3{slash}TOSC1)") (class "Default")
      (node (ref "IC2") (pin "13") (pinfunction "PB3/TOSC1_13") (pintype "passive"))
      (node (ref "R16") (pin "1") (pinfunction "1_1") (pintype "passive"))
    )
    (net (code "43") (name "Net-(J2-CC1)") (class "Default")
      (node (ref "J2") (pin "A5") (pinfunction "CC1_A5") (pintype "bidirectional"))
      (node (ref "R30") (pin "1") (pinfunction "1_1") (pintype "passive"))
    )
    (net (code "44") (name "Net-(Q1-B)") (class "Default")
      (node (ref "Q1") (pin "1") (pinfunction "B_1") (pintype "passive"))
      (node (ref "R11") (pin "1") (pinfunction "1_1") (pintype "passive"))
      (node (ref "R8") (pin "2") (pinfunction "2_2") (pintype "passive"))
    )
    (net (code "45") (name "Net-(Q1-C)") (class "Default")
      (node (ref "C4") (pin "1") (pinfunction "1_1") (pintype "passive"))
      (node (ref "Q1") (pin "2") (pinfunction "C_2") (pintype "passive"))
      (node (ref "R3") (pin "2") (pinfunction "2_2") (pintype "passive"))
      (node (ref "R4") (pin "2") (pinfunction "2_2") (pintype "passive"))
    )
    (net (code "46") (name "Net-(Q2-G)") (class "Default")
      (node (ref "Q2") (pin "3") (pinfunction "G_3") (pintype "passive"))
      (node (ref "R10") (pin "2") (pinfunction "2_2") (pintype "passive"))
      (node (ref "R14") (pin "1") (pinfunction "1_1") (pintype "passive"))
    )
    (net (code "47") (name "Net-(Q3-B)") (class "Default")
      (node (ref "C10") (pin "1") (pinfunction "1_1") (pintype "passive"))
      (node (ref "Q3") (pin "1") (pinfunction "B_1") (pintype "passive"))
      (node (ref "R18") (pin "1") (pinfunction "1_1") (pintype "passive"))
      (node (ref "R19") (pin "2") (pinfunction "2_2") (pintype "passive"))
    )
    (net (code "48") (name "Net-(Q3-C)") (class "Default")
      (node (ref "Q3") (pin "2") (pinfunction "C_2") (pintype "passive"))
      (node (ref "R14") (pin "2") (pinfunction "2_2") (pintype "passive"))
    )
    (net (code "49") (name "Net-(R12-Pad1)") (class "Default")
      (node (ref "R12") (pin "1") (pinfunction "1_1") (pintype "passive"))
      (node (ref "R8") (pin "1") (pinfunction "1_1") (pintype "passive"))
      (node (ref "S1") (pin "1") (pinfunction "1_1") (pintype "passive"))
    )
    (net (code "50") (name "Net-(U1-SW)") (class "Default")
      (node (ref "L1") (pin "1") (pinfunction "1_1") (pintype "passive"))
      (node (ref "U1") (pin "5") (pinfunction "SW_5") (pintype "passive"))
    )
    (net (code "51") (name "Net-(U2-TXD)") (class "Default")
      (node (ref "R5") (pin "2") (pinfunction "2_2") (pintype "passive"))
      (node (ref "U2") (pin "6") (pinfunction "TXD_6") (pintype "passive"))
    )
    (net (code "52") (name "Net-(U2-V3)") (class "Default")
      (node (ref "C8") (pin "1") (pinfunction "1_1") (pintype "passive"))
      (node (ref "U2") (pin "8") (pinfunction "V3_8") (pintype "passive"))
    )
    (net (code "53") (name "Net-(U3-PROG)") (class "Default")
      (node (ref "R31") (pin "1") (pinfunction "1_1") (pintype "passive"))
      (node (ref "U3") (pin "2") (pinfunction "PROG_2") (pintype "bidirectional"))
    )
    (net (code "54") (name "VBUS") (class "Default")
      (node (ref "J2") (pin "A4_B9") (pinfunction "VBUS_A4_B9") (pintype "power_in"))
      (node (ref "J2") (pin "B4_A9") (pinfunction "VBUS_B4_A9") (pintype "power_in"))
      (node (ref "R26") (pin "1") (pinfunction "1_1") (pintype "passive"))
    )
    (net (code "55") (name "VBUS_IN") (class "Default")
      (node (ref "C14") (pin "2") (pinfunction "2_2") (pintype "passive"))
      (node (ref "R26") (pin "2") (pinfunction "2_2") (pintype "passive"))
      (node (ref "R28") (pin "1") (pinfunction "1_1") (pintype "passive"))
      (node (ref "R29") (pin "1") (pinfunction "1_1") (pintype "passive"))
      (node (ref "U3") (pin "4") (pinfunction "VCC_4") (pintype "power_in"))
      (node (ref "U3") (pin "8") (pinfunction "CE_8") (pintype "input"))
    )
    (net (code "56") (name "VOUT") (class "Default")
      (node (ref "C1") (pin "2") (pinfunction "2_2") (pintype "passive"))
      (node (ref "L1") (pin "2") (pinfunction "2_2") (pintype "passive"))
      (node (ref "Q2") (pin "6") (pinfunction "D@4_6") (pintype "passive"))
      (node (ref "U1") (pin "1") (pinfunction "EN_1") (pintype "passive"))
      (node (ref "U1") (pin "8") (pinfunction "VIN_8") (pintype "passive"))
    )
    (net (code "57") (name "unconnected-(IC1-3V3-Pad6)") (class "Default")
      (node (ref "IC1") (pin "6") (pinfunction "3V3_6") (pintype "passive+no_connect"))
    )
    (net (code "58") (name "unconnected-(IC1-PA3-Pad1)") (class "Default")
      (node (ref "IC1") (pin "1") (pinfunction "PA3_1") (pintype "passive+no_connect"))
    )
    (net (code "59") (name "unconnected-(IC1-PA4-Pad2)") (class "Default")
      (node (ref "IC1") (pin "2") (pinfunction "PA4_2") (pintype "passive+no_connect"))
    )
    (net (code "60") (name "unconnected-(IC1-PA5-Pad3)") (class "Default")
      (node (ref "IC1") (pin "3") (pinfunction "PA5_3") (pintype "passive+no_connect"))
    )
    (net (code "61") (name "unconnected-(IC1-PB2-Pad24)") (class "Default")
      (node (ref "IC1") (pin "24") (pinfunction "PB2_24") (pintype "passive+no_connect"))
    )
    (net (code "62") (name "unconnected-(IC1-PB4-Pad22)") (class "Default")
      (node (ref "IC1") (pin "22") (pinfunction "PB4_22") (pintype "passive+no_connect"))
    )
    (net (code "63") (name "unconnected-(IC1-PB5-Pad21)") (class "Default")
      (node (ref "IC1") (pin "21") (pinfunction "PB5_21") (pintype "passive+no_connect"))
    )
    (net (code "64") (name "unconnected-(IC1-PB6-Pad20)") (class "Default")
      (node (ref "IC1") (pin "20") (pinfunction "PB6_20") (pintype "passive+no_connect"))
    )
    (net (code "65") (name "unconnected-(IC1-PC1-Pad14)") (class "Default")
      (node (ref "IC1") (pin "14") (pinfunction "PC1_14") (pintype "passive"))
    )
    (net (code "66") (name "unconnected-(IC1-PC3-Pad15)") (class "Default")
      (node (ref "IC1") (pin "15") (pinfunction "PC3_15") (pintype "passive+no_connect"))
    )
    (net (code "67") (name "unconnected-(IC1-PC4-Pad16)") (class "Default")
      (node (ref "IC1") (pin "16") (pinfunction "PC4_16") (pintype "passive+no_connect"))
    )
    (net (code "68") (name "unconnected-(IC1-PC5-Pad17)") (class "Default")
      (node (ref "IC1") (pin "17") (pinfunction "PC5_17") (pintype "passive+no_connect"))
    )
    (net (code "69") (name "unconnected-(IC1-PR1-Pad19)") (class "Default")
      (node (ref "IC1") (pin "19") (pinfunction "PR1_19") (pintype "passive+no_connect"))
    )
    (net (code "70") (name "unconnected-(IC1-PR2-Pad18)") (class "Default")
      (node (ref "IC1") (pin "18") (pinfunction "PR2_18") (pintype "passive+no_connect"))
    )
    (net (code "71") (name "unconnected-(IC2-EXTCLK_{slash}PA3-Pad2)") (class "Default")
      (node (ref "IC2") (pin "2") (pinfunction "EXTCLK_/PA3_2") (pintype "passive+no_connect"))
    )
    (net (code "72") (name "unconnected-(IC2-PA1-Pad24)") (class "Default")
      (node (ref "IC2") (pin "24") (pinfunction "PA1_24") (pintype "passive+no_connect"))
    )
    (net (code "73") (name "unconnected-(IC2-PA4-Pad5)") (class "Default")
      (node (ref "IC2") (pin "5") (pinfunction "PA4_5") (pintype "passive+no_connect"))
    )
    (net (code "74") (name "unconnected-(IC2-PA7-Pad8)") (class "Default")
      (node (ref "IC2") (pin "8") (pinfunction "PA7_8") (pintype "passive+no_connect"))
    )
    (net (code "75") (name "unconnected-(IC2-PB1-Pad15)") (class "Default")
      (node (ref "IC2") (pin "15") (pinfunction "PB1_15") (pintype "passive+no_connect"))
    )
    (net (code "76") (name "unconnected-(IC2-PB4-Pad12)") (class "Default")
      (node (ref "IC2") (pin "12") (pinfunction "PB4_12") (pintype "passive+no_connect"))
    )
    (net (code "77") (name "unconnected-(IC2-PB7-Pad9)") (class "Default")
      (node (ref "IC2") (pin "9") (pinfunction "PB7_9") (pintype "passive+no_connect"))
    )
    (net (code "78") (name "unconnected-(IC2-PC3-Pad20)") (class "Default")
      (node (ref "IC2") (pin "20") (pinfunction "PC3_20") (pintype "passive+no_connect"))
    )
    (net (code "79") (name "unconnected-(IC2-PC4-Pad21)") (class "Default")
      (node (ref "IC2") (pin "21") (pinfunction "PC4_21") (pintype "passive+no_connect"))
    )
    (net (code "80") (name "unconnected-(IC2-PC5-Pad22)") (class "Default")
      (node (ref "IC2") (pin "22") (pinfunction "PC5_22") (pintype "passive+no_connect"))
    )
    (net (code "81") (name "unconnected-(J1-CC1-PadA5)") (class "Default")
      (node (ref "J1") (pin "A5") (pinfunction "CC1_A5") (pintype "bidirectional+no_connect"))
    )
    (net (code "82") (name "unconnected-(J1-CC2-PadB5)") (class "Default")
      (node (ref "J1") (pin "B5") (pinfunction "CC2_B5") (pintype "bidirectional+no_connect"))
    )
    (net (code "83") (name "unconnected-(J1-DN2-PadB7)") (class "Default")
      (node (ref "J1") (pin "B7") (pinfunction "DN2_B7") (pintype "bidirectional+no_connect"))
    )
    (net (code "84") (name "unconnected-(J1-DP2-PadB6)") (class "Default")
      (node (ref "J1") (pin "B6") (pinfunction "DP2_B6") (pintype "bidirectional+no_connect"))
    )
    (net (code "85") (name "unconnected-(J1-SBU1-PadA8)") (class "Default")
      (node (ref "J1") (pin "A8") (pinfunction "SBU1_A8") (pintype "bidirectional+no_connect"))
    )
    (net (code "86") (name "unconnected-(J1-SBU2-PadB8)") (class "Default")
      (node (ref "J1") (pin "B8") (pinfunction "SBU2_B8") (pintype "bidirectional+no_connect"))
    )
    (net (code "87") (name "unconnected-(J2-CC2-PadB5)") (class "Default")
      (node (ref "J2") (pin "B5") (pinfunction "CC2_B5") (pintype "bidirectional+no_connect"))
    )
    (net (code "88") (name "unconnected-(J2-DN1-PadA7)") (class "Default")
      (node (ref "J2") (pin "A7") (pinfunction "DN1_A7") (pintype "bidirectional+no_connect"))
    )
    (net (code "89") (name "unconnected-(J2-DP1-PadA6)") (class "Default")
      (node (ref "J2") (pin "A6") (pinfunction "DP1_A6") (pintype "bidirectional+no_connect"))
    )
    (net (code "90") (name "unconnected-(J2-SBU1-PadA8)") (class "Default")
      (node (ref "J2") (pin "A8") (pinfunction "SBU1_A8") (pintype "bidirectional+no_connect"))
    )
    (net (code "91") (name "unconnected-(J2-SBU2-PadB8)") (class "Default")
      (node (ref "J2") (pin "B8") (pinfunction "SBU2_B8") (pintype "bidirectional+no_connect"))
    )
    (net (code "92") (name "unconnected-(Q2-D@1-Pad1)") (class "Default")
      (node (ref "Q2") (pin "1") (pinfunction "D@1_1") (pintype "passive"))
    )
    (net (code "93") (name "unconnected-(Q2-D@2-Pad2)") (class "Default")
      (node (ref "Q2") (pin "2") (pinfunction "D@2_2") (pintype "passive"))
    )
    (net (code "94") (name "unconnected-(Q2-D@3-Pad5)") (class "Default")
      (node (ref "Q2") (pin "5") (pinfunction "D@3_5") (pintype "passive"))
    )
    (net (code "95") (name "unconnected-(U1-NC-Pad2)") (class "Default")
      (node (ref "U1") (pin "2") (pinfunction "NC_2") (pintype "passive+no_connect"))
    )
    (net (code "96") (name "unconnected-(U1-PG-Pad3)") (class "Default")
      (node (ref "U1") (pin "3") (pinfunction "PG_3") (pintype "passive+no_connect"))
    )
    (net (code "97") (name "unconnected-(U2-RTS#-Pad4)") (class "Default")
      (node (ref "U2") (pin "4") (pinfunction "RTS#_4") (pintype "passive+no_connect"))
    )
  )
)
